# 3_3VBuck_1117_P1.net
KiCad netlist of a schematic drawn in EasyEDA Pro
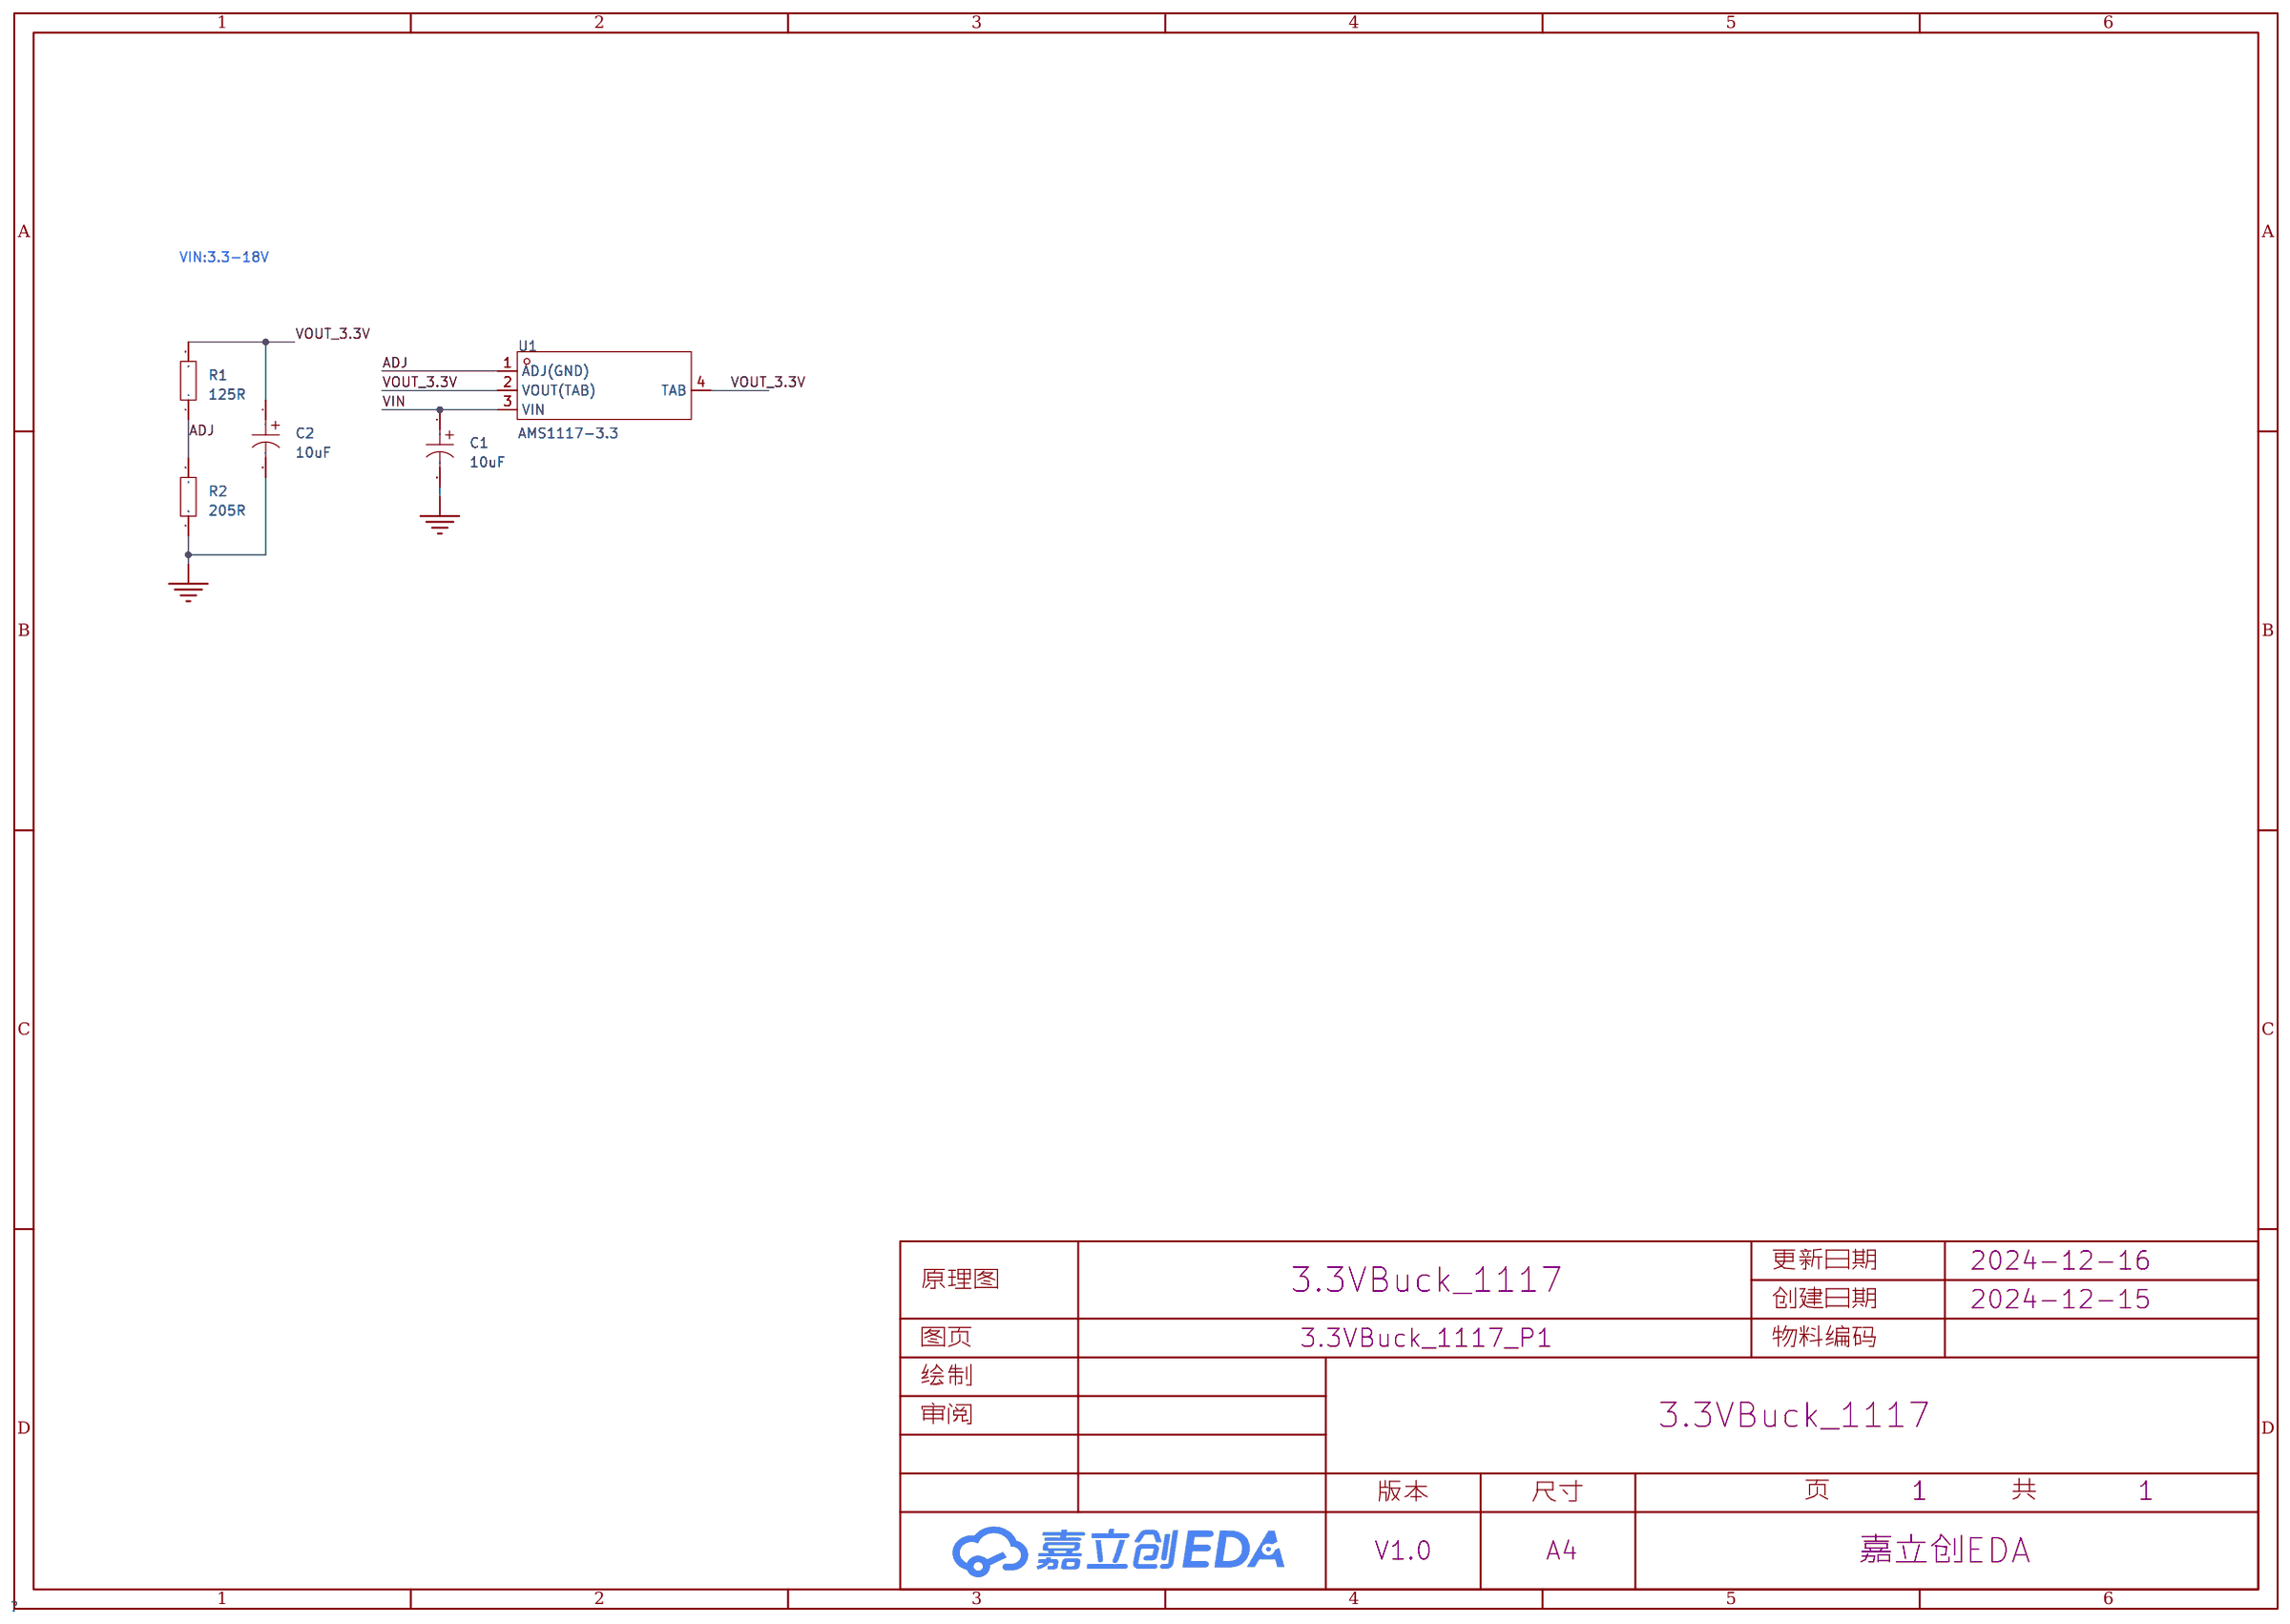
[diagram p0: schematic sheet]

(export (version "E")
  (design (tool "Eeschema 10.0.6"))
  (components
    (comp (ref "C1")
      (value "10uF")
      (footprint "easyedapro:CAP-SMD_L2.0-W1.3-FD")
      (description "容值:10uF;精度:±20%;额定电压:10V;等效串联电阻:5.9Ω@100kHz;")
      (fields (field (name "Manufacturer Part") "TMCP1A106MTRF") (field (name "Manufacturer") "VISHAY(威世)"))
      (libsource (lib "easyedapro") (part "TMCP1A106MTRF"))
    )
    (comp (ref "C2")
      (value "10uF")
      (footprint "easyedapro:CAP-SMD_L2.0-W1.3-FD")
      (description "容值:10uF;精度:±20%;额定电压:10V;等效串联电阻:5.9Ω@100kHz;")
      (fields (field (name "Manufacturer Part") "TMCP1A106MTRF") (field (name "Manufacturer") "VISHAY(威世)"))
      (libsource (lib "easyedapro") (part "TMCP1A106MTRF"))
    )
    (comp (ref "R1") (value "125R") (footprint "easyedapro:R0805") (libsource (lib "easyedapro") (part "电阻")))
    (comp (ref "R2") (value "205R") (footprint "easyedapro:R0805") (libsource (lib "easyedapro") (part "电阻")))
    (comp (ref "U1")
      (value "AMS1117-3.3")
      (footprint "easyedapro:SOT-223-4_L6.5-W3.5-P2.30-LS7.0-BR")
      (description "输出类型:固定;最大输入电压:18V;输出电压:3.3V;输出电流:1A;电源纹波抑制比(PSRR):60dB@(120Hz);输出极性:正极;")
      (fields (field (name "Manufacturer") "UMW(友台半导体)"))
      (libsource (lib "easyedapro") (part "AMS1117-3.3_C347222"))
    )
  )
  (nets
    (net (code "1") (name "/ADJ") (class "Default")
      (node (ref "R1") (pin "1") (pinfunction "1_1") (pintype "input"))
      (node (ref "R2") (pin "2") (pinfunction "2_2") (pintype "input"))
      (node (ref "U1") (pin "1") (pinfunction "ADJ(GND)_1") (pintype "unspecified"))
    )
    (net (code "2") (name "/VIN") (class "Default")
      (node (ref "C1") (pin "1") (pinfunction "1_1") (pintype "input"))
      (node (ref "U1") (pin "3") (pinfunction "VIN_3") (pintype "unspecified"))
    )
    (net (code "3") (name "/VOUT_3.3V") (class "Default")
      (node (ref "C2") (pin "1") (pinfunction "1_1") (pintype "input"))
      (node (ref "R1") (pin "2") (pinfunction "2_2") (pintype "input"))
      (node (ref "U1") (pin "2") (pinfunction "VOUT(TAB)_2") (pintype "unspecified"))
      (node (ref "U1") (pin "4") (pinfunction "TAB_4") (pintype "unspecified"))
    )
    (net (code "4") (name "GND") (class "Default")
      (node (ref "C1") (pin "2") (pinfunction "2_2") (pintype "input"))
      (node (ref "C2") (pin "2") (pinfunction "2_2") (pintype "input"))
      (node (ref "R2") (pin "1") (pinfunction "1_1") (pintype "input"))
    )
  )
)
